# Fuente_de_Poder_Taylor.net
KiCad netlist of a schematic drawn in EAGLE
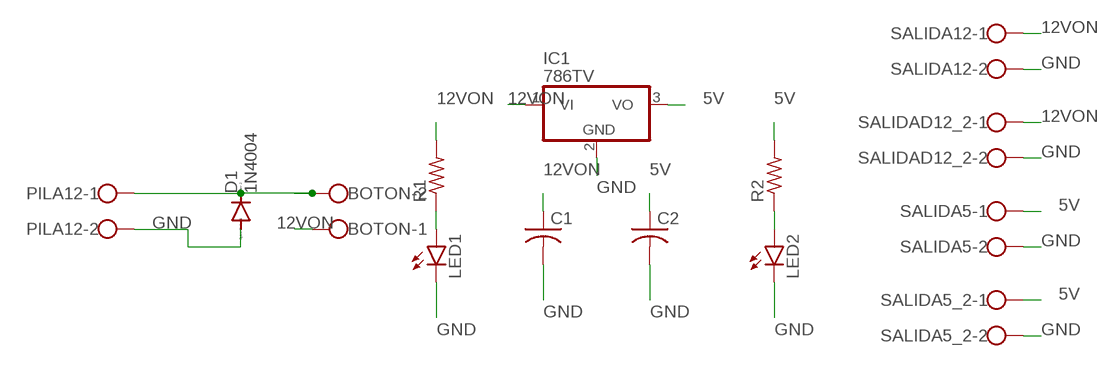
[diagram p0: schematic, sheet 1]

(export (version "E")
  (design (tool "Eeschema 10.0.6"))
  (components
    (comp (ref "BOTON")
      (value "W237-102")
      (footprint "eagle-import:W237-102")
      (fields (field (name "MPN") "237-102"))
      (libsource (lib "eagle-import") (part "W237-102"))
    )
    (comp (ref "C1")
      (value "C-US025-024X044")
      (footprint "eagle-import:C025-024X044")
      (libsource (lib "eagle-import") (part "C-US025-024X044"))
    )
    (comp (ref "C2")
      (value "C-US025-024X044")
      (footprint "eagle-import:C025-024X044")
      (libsource (lib "eagle-import") (part "C-US025-024X044"))
    )
    (comp (ref "D1")
      (value "1N4004")
      (footprint "eagle-import:DO41-10")
      (libsource (lib "eagle-import") (part "1N4004"))
    )
    (comp (ref "IC1")
      (value "786TV")
      (footprint "eagle-import:TO220V")
      (libsource (lib "eagle-import") (part "78TV6"))
    )
    (comp (ref "LED1")
      (value "LED3MM")
      (footprint "eagle-import:LED3MM")
      (libsource (lib "eagle-import") (part "LED3MM"))
    )
    (comp (ref "LED2")
      (value "LED3MM")
      (footprint "eagle-import:LED3MM")
      (libsource (lib "eagle-import") (part "LED3MM"))
    )
    (comp (ref "PILA12")
      (value "W237-102")
      (footprint "eagle-import:W237-102")
      (fields (field (name "MPN") "237-102") (field (name "SPICEPREFIX") "X"))
      (libsource (lib "eagle-import") (part "W237-102"))
    )
    (comp (ref "R1")
      (value "R-US_0204/7")
      (footprint "eagle-import:0204_7")
      (libsource (lib "eagle-import") (part "R-US_0204/7"))
    )
    (comp (ref "R2")
      (value "R-US_0204/7")
      (footprint "eagle-import:0204_7")
      (libsource (lib "eagle-import") (part "R-US_0204/7"))
    )
    (comp (ref "SALIDA5")
      (value "W237-102")
      (footprint "eagle-import:W237-102")
      (fields (field (name "MPN") "237-102"))
      (libsource (lib "eagle-import") (part "W237-102"))
    )
    (comp (ref "SALIDA5_2")
      (value "W237-102")
      (footprint "eagle-import:W237-102")
      (fields (field (name "MPN") "237-102"))
      (libsource (lib "eagle-import") (part "W237-102"))
    )
    (comp (ref "SALIDA12")
      (value "W237-102")
      (footprint "eagle-import:W237-102")
      (fields (field (name "MPN") "237-102"))
      (libsource (lib "eagle-import") (part "W237-102"))
    )
    (comp (ref "SALIDAD12_2")
      (value "W237-102")
      (footprint "eagle-import:W237-102")
      (fields (field (name "MPN") "237-102"))
      (libsource (lib "eagle-import") (part "W237-102"))
    )
  )
  (nets
    (net (code "1") (name "/5V") (class "Default")
      (node (ref "C2") (pin "1") (pinfunction "1_1") (pintype "passive"))
      (node (ref "IC1") (pin "3") (pinfunction "VO_3") (pintype "passive"))
      (node (ref "R2") (pin "2") (pinfunction "2_2") (pintype "passive"))
      (node (ref "SALIDA5") (pin "1") (pinfunction "KL_1") (pintype "passive"))
      (node (ref "SALIDA5_2") (pin "1") (pinfunction "KL_1") (pintype "passive"))
    )
    (net (code "2") (name "/12VON") (class "Default")
      (node (ref "BOTON") (pin "1") (pinfunction "KL_1") (pintype "passive"))
      (node (ref "C1") (pin "1") (pinfunction "1_1") (pintype "passive"))
      (node (ref "IC1") (pin "1") (pinfunction "VI_1") (pintype "input"))
      (node (ref "R1") (pin "2") (pinfunction "2_2") (pintype "passive"))
      (node (ref "SALIDA12") (pin "1") (pinfunction "KL_1") (pintype "passive"))
      (node (ref "SALIDAD12_2") (pin "1") (pinfunction "KL_1") (pintype "passive"))
    )
    (net (code "3") (name "/GND") (class "Default")
      (node (ref "C1") (pin "2") (pinfunction "2_2") (pintype "passive"))
      (node (ref "C2") (pin "2") (pinfunction "2_2") (pintype "passive"))
      (node (ref "D1") (pin "A") (pinfunction "A_A") (pintype "passive"))
      (node (ref "IC1") (pin "2") (pinfunction "GND_2") (pintype "passive"))
      (node (ref "LED1") (pin "K") (pinfunction "C_K") (pintype "passive"))
      (node (ref "LED2") (pin "K") (pinfunction "C_K") (pintype "passive"))
      (node (ref "PILA12") (pin "2") (pinfunction "KL_2") (pintype "passive"))
      (node (ref "SALIDA12") (pin "2") (pinfunction "KL_2") (pintype "passive"))
      (node (ref "SALIDA5") (pin "2") (pinfunction "KL_2") (pintype "passive"))
      (node (ref "SALIDA5_2") (pin "2") (pinfunction "KL_2") (pintype "passive"))
      (node (ref "SALIDAD12_2") (pin "2") (pinfunction "KL_2") (pintype "passive"))
    )
    (net (code "4") (name "Net-(BOTONB-KL)") (class "Default")
      (node (ref "BOTON") (pin "2") (pinfunction "KL_2") (pintype "passive"))
      (node (ref "D1") (pin "C") (pinfunction "C_C") (pintype "passive"))
      (node (ref "PILA12") (pin "1") (pinfunction "KL_1") (pintype "passive"))
    )
    (net (code "5") (name "Net-(LED1-PadA)") (class "Default")
      (node (ref "LED1") (pin "A") (pinfunction "A_A") (pintype "passive"))
      (node (ref "R1") (pin "1") (pinfunction "1_1") (pintype "passive"))
    )
    (net (code "6") (name "Net-(LED2-PadA)") (class "Default")
      (node (ref "LED2") (pin "A") (pinfunction "A_A") (pintype "passive"))
      (node (ref "R2") (pin "1") (pinfunction "1_1") (pintype "passive"))
    )
  )
)
